# schematicEagle-CORRECTED.net
KiCad netlist of a schematic drawn in EAGLE
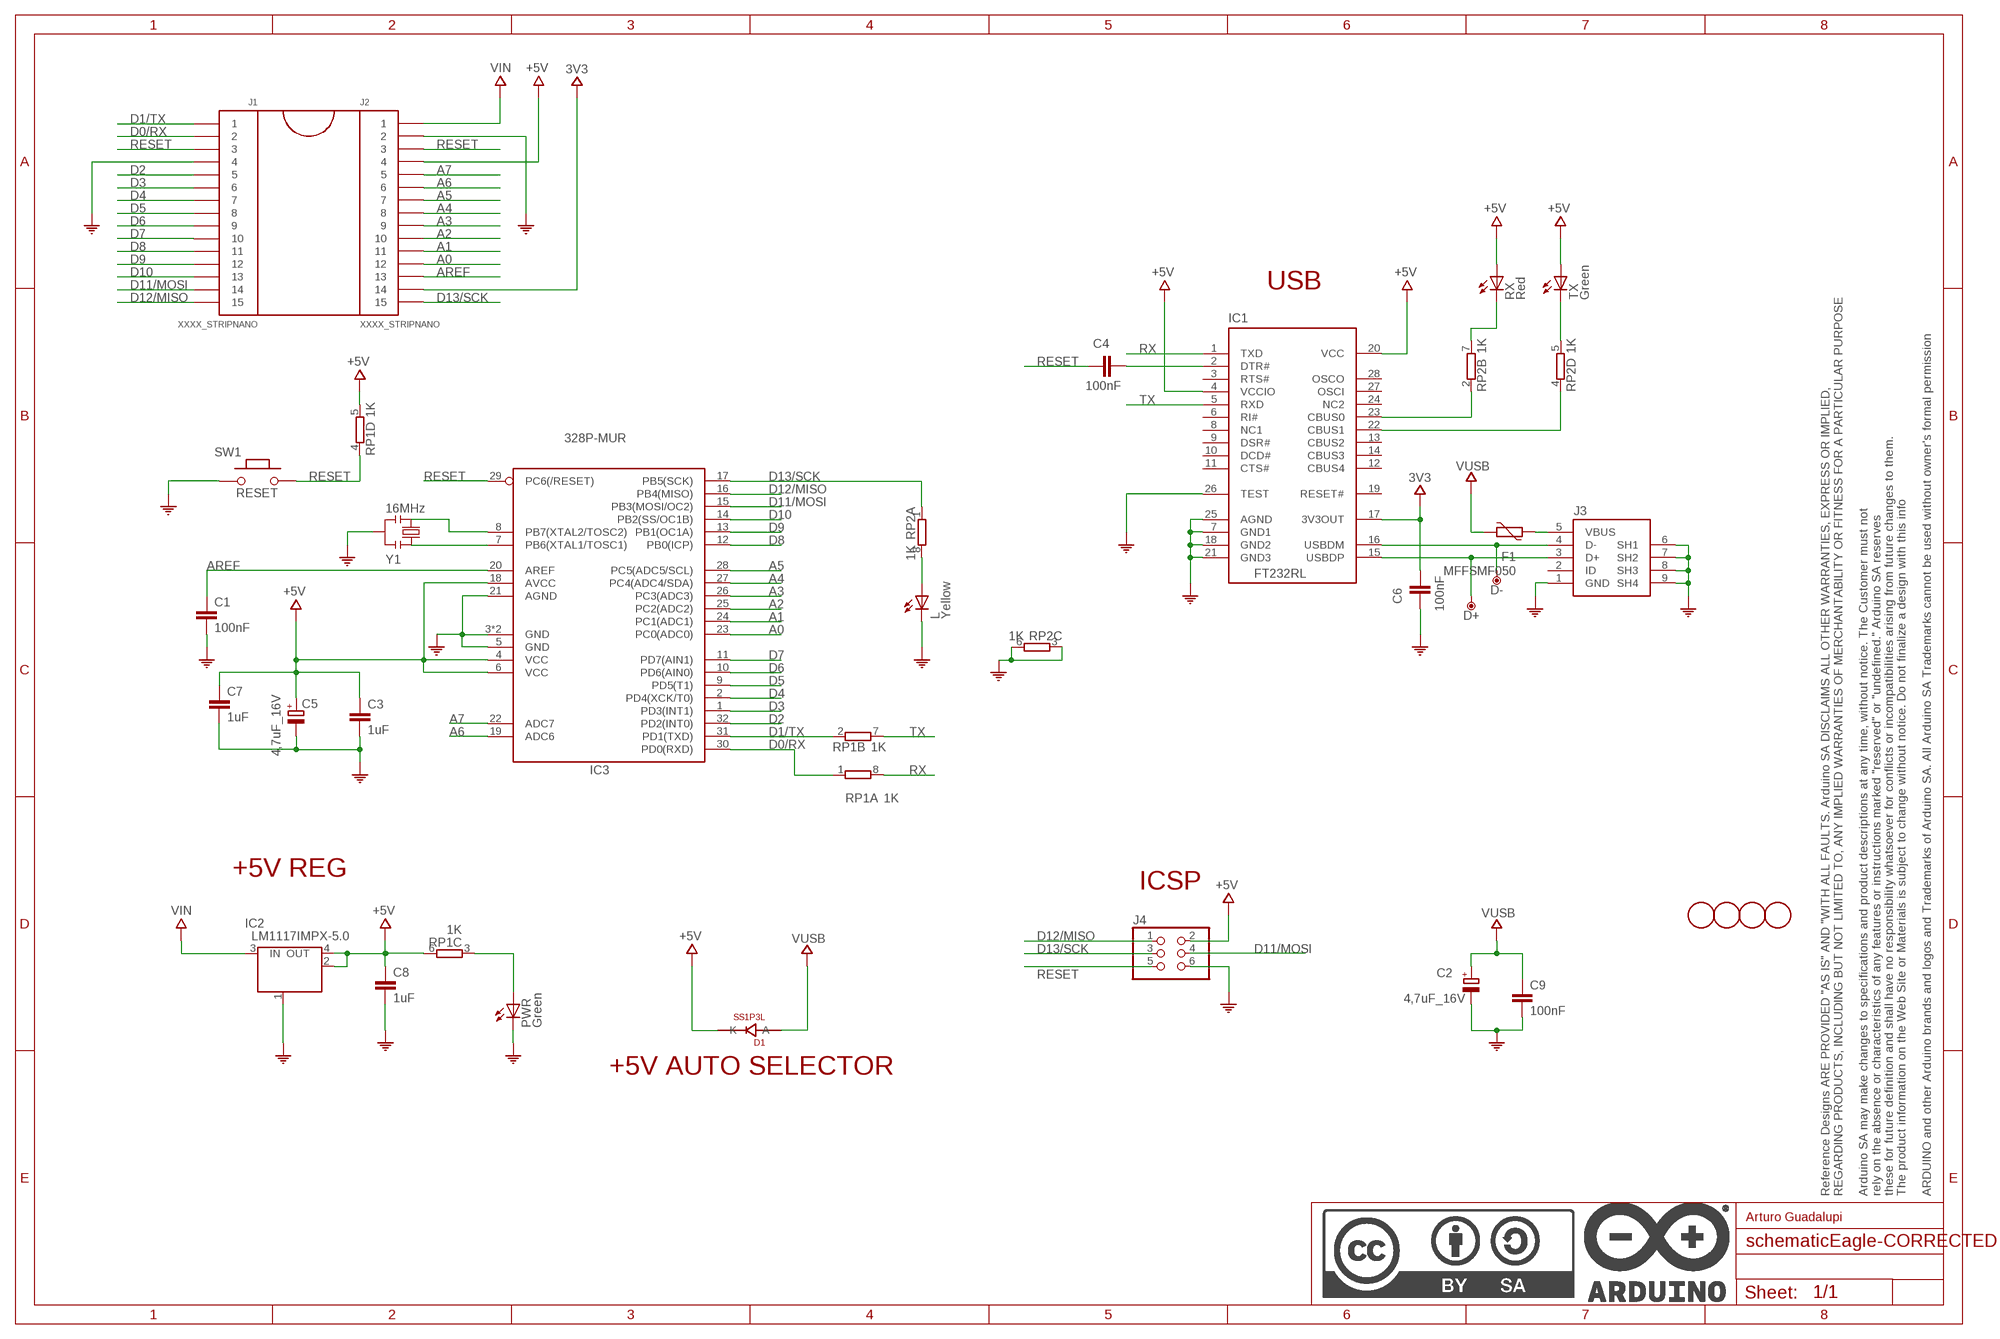
[diagram p0: schematic, sheet 1]

(export (version "E")
  (design (tool "Eeschema 10.0.6"))
  (components
    (comp (ref "C1")
      (value "100nF")
      (footprint "eagle-import:C0603-ROUND")
      (fields (field (name "PART_NUMBER") "cl10b104kbnc"))
      (libsource (lib "eagle-import") (part "0015_100NF_0603"))
    )
    (comp (ref "C2")
      (value "4,7uF_16V")
      (footprint "eagle-import:TAN-A")
      (fields (field (name "PART_NUMBER") "TAJA475MO16RNJ"))
      (libsource (lib "eagle-import") (part "0833_TAJA475MO16RNJ"))
    )
    (comp (ref "C3")
      (value "1uF")
      (footprint "eagle-import:C0603-ROUND")
      (fields (field (name "PART_NUMBER") "1uF_0603/GRM188R61E105KA12D"))
      (libsource (lib "eagle-import") (part "0006_1UF_0603/GRM188R61E105KA12D"))
    )
    (comp (ref "C4")
      (value "100nF")
      (footprint "eagle-import:C0603-ROUND")
      (fields (field (name "PART_NUMBER") "cl10b104kbnc"))
      (libsource (lib "eagle-import") (part "0015_100NF_0603"))
    )
    (comp (ref "C5")
      (value "4,7uF_16V")
      (footprint "eagle-import:TAN-A")
      (fields (field (name "PART_NUMBER") "TAJA475MO16RNJ"))
      (libsource (lib "eagle-import") (part "0833_TAJA475MO16RNJ"))
    )
    (comp (ref "C6")
      (value "100nF")
      (footprint "eagle-import:C0603-ROUND")
      (fields (field (name "PART_NUMBER") "cl10b104kbnc"))
      (libsource (lib "eagle-import") (part "0015_100NF_0603"))
    )
    (comp (ref "C7")
      (value "1uF")
      (footprint "eagle-import:C0603-ROUND")
      (fields (field (name "PART_NUMBER") "1uF_0603/GRM188R61E105KA12D"))
      (libsource (lib "eagle-import") (part "0006_1UF_0603/GRM188R61E105KA12D"))
    )
    (comp (ref "C8")
      (value "1uF")
      (footprint "eagle-import:C0603-ROUND")
      (fields (field (name "PART_NUMBER") "1uF_0603/GRM188R61E105KA12D"))
      (libsource (lib "eagle-import") (part "0006_1UF_0603/GRM188R61E105KA12D"))
    )
    (comp (ref "C9")
      (value "100nF")
      (footprint "eagle-import:C0603-ROUND")
      (fields (field (name "PART_NUMBER") "cl10b104kbnc"))
      (libsource (lib "eagle-import") (part "0015_100NF_0603"))
    )
    (comp (ref "D+")
      (value "DNP")
      (footprint "eagle-import:TP-1.00MM")
      (libsource (lib "eagle-import") (part "TPTP-1.00MM"))
    )
    (comp (ref "D-")
      (value "DNP")
      (footprint "eagle-import:TP-1.00MM")
      (libsource (lib "eagle-import") (part "TPTP-1.00MM"))
    )
    (comp (ref "D1")
      (value "SS1P3L")
      (footprint "eagle-import:DO220AAL")
      (fields (field (name "PART_NUMBER") "SS1P3L-M3/84A"))
      (libsource (lib "eagle-import") (part "0025_SS1P3L-M3/84A"))
    )
    (comp (ref "F1")
      (value "MFFSMF050")
      (footprint "eagle-import:0603-1608X90N")
      (fields (field (name "MANUFACTURER") "Bourns Inc "))
      (libsource (lib "eagle-import") (part "PTC"))
    )
    (comp (ref "FRAME1")
      (value "DNP")
      (footprint "eagle-import:FRAME")
      (libsource (lib "eagle-import") (part "A3-FRAME"))
    )
    (comp (ref "IC1")
      (value "FT232RL")
      (footprint "eagle-import:SSOP28")
      (libsource (lib "eagle-import") (part "0226_FT232RL"))
    )
    (comp (ref "IC2")
      (value "LM1117IMPX-5.0")
      (footprint "eagle-import:LINEAR_SOT223")
      (libsource (lib "eagle-import") (part "0022_LM1117IMPX-5.0"))
    )
    (comp (ref "IC3")
      (value "328P-MUR")
      (footprint "eagle-import:VQFN32")
      (fields (field (name "MANUFACTURER") "ATMEL"))
      (libsource (lib "eagle-import") (part "ATMEGA328P-32MUR"))
    )
    (comp (ref "J1")
      (value "XXXX_STRIPNANO")
      (footprint "eagle-import:HEAD15-NOSS")
      (libsource (lib "eagle-import") (part "XXXX_STRIPNANO"))
    )
    (comp (ref "J2")
      (value "XXXX_STRIPNANO")
      (footprint "eagle-import:HEAD15-NOSS")
      (libsource (lib "eagle-import") (part "XXXX_STRIPNANO"))
    )
    (comp (ref "J3")
      (value "0219_14850")
      (footprint "eagle-import:USB-MINI-B_2")
      (fields (field (name "PART_NUMBER") "14850"))
      (libsource (lib "eagle-import") (part "0219_14850"))
    )
    (comp (ref "J4")
      (value "0114_PH254-203DF118A00V")
      (footprint "eagle-import:2X03")
      (fields (field (name "PART_NUMBER") "PH254-203DF118A00V"))
      (libsource (lib "eagle-import") (part "0114_PH254-203DF118A00V"))
    )
    (comp (ref "L")
      (value "Yellow")
      (footprint "eagle-import:CHIPLED_0805")
      (fields (field (name "PART_NUMBER") "KPT-2012YC"))
      (libsource (lib "eagle-import") (part "0044_KPT-2012YC"))
    )
    (comp (ref "PWR")
      (value "Green")
      (footprint "eagle-import:CHIPLED_0805")
      (fields (field (name "PART_NUMBER") "KPT-2012SGC"))
      (libsource (lib "eagle-import") (part "0043_KPT-2012SGC"))
    )
    (comp (ref "RP1")
      (value "1K")
      (footprint "eagle-import:CAY16")
      (fields (field (name "PART_NUMBER") "064R_1K_/_CAY16-102J4LF"))
      (libsource (lib "eagle-import") (part "0005_064R_1K_/_CAY16-102J4LF"))
    )
    (comp (ref "RP2")
      (value "1K")
      (footprint "eagle-import:CAY16")
      (fields (field (name "PART_NUMBER") "064R_1K_/_CAY16-102J4LF"))
      (libsource (lib "eagle-import") (part "0005_064R_1K_/_CAY16-102J4LF"))
    )
    (comp (ref "RX")
      (value "Red")
      (footprint "eagle-import:CHIPLED_0805")
      (fields (field (name "PART_NUMBER") "KTP-2012SURCK"))
      (libsource (lib "eagle-import") (part "0181_KTP-2012SURCK"))
    )
    (comp (ref "SW1")
      (value "RESET")
      (footprint "eagle-import:SMD_157SW")
      (fields (field (name "PART_NUMBER") "IT-1185AP1C-160G-G_T&R"))
      (libsource (lib "eagle-import") (part "0173_IT-1185AP1C-160G-G_T&R"))
    )
    (comp (ref "TX")
      (value "Green")
      (footprint "eagle-import:CHIPLED_0805")
      (fields (field (name "PART_NUMBER") "KPT-2012SGC"))
      (libsource (lib "eagle-import") (part "0043_KPT-2012SGC"))
    )
    (comp (ref "U$4")
      (value "DNP")
      (footprint "eagle-import:FD-1-1.5")
      (libsource (lib "eagle-import") (part "FIDUCIAL-1.5MM"))
    )
    (comp (ref "U$5")
      (value "DNP")
      (footprint "eagle-import:FD-1-1.5")
      (libsource (lib "eagle-import") (part "FIDUCIAL-1.5MM"))
    )
    (comp (ref "U$53")
      (value "DNP")
      (footprint "eagle-import:FD-1-1.5")
      (libsource (lib "eagle-import") (part "FIDUCIAL-1.5MM"))
    )
    (comp (ref "U$54")
      (value "DNP")
      (footprint "eagle-import:FD-1-1.5")
      (libsource (lib "eagle-import") (part "FIDUCIAL-1.5MM"))
    )
    (comp (ref "Y1")
      (value "16MHz")
      (footprint "eagle-import:RESONATOR")
      (fields (field (name "PART_NUMBER") "CSTCE16M0V53-R0"))
      (libsource (lib "eagle-import") (part "0011_CSTCE16M0V53-R0"))
    )
  )
  (nets
    (net (code "1") (name "+5V") (class "Default")
      (node (ref "C3") (pin "1") (pinfunction "1_1") (pintype "passive"))
      (node (ref "C5") (pin "1") (pinfunction "+_1") (pintype "passive"))
      (node (ref "C7") (pin "1") (pinfunction "1_1") (pintype "passive"))
      (node (ref "C8") (pin "1") (pinfunction "1_1") (pintype "passive"))
      (node (ref "D1") (pin "P$1") (pinfunction "K_P$1") (pintype "bidirectional"))
      (node (ref "IC1") (pin "20") (pinfunction "VCC_20") (pintype "power_in"))
      (node (ref "IC1") (pin "4") (pinfunction "VCCIO_4") (pintype "power_in"))
      (node (ref "IC2") (pin "2") (pinfunction "OUT_2") (pintype "passive"))
      (node (ref "IC2") (pin "4") (pinfunction "OUT_4") (pintype "passive"))
      (node (ref "IC3") (pin "18") (pinfunction "AVCC_18") (pintype "bidirectional"))
      (node (ref "IC3") (pin "4") (pinfunction "VCC_4") (pintype "bidirectional"))
      (node (ref "IC3") (pin "6") (pinfunction "VCC_6") (pintype "bidirectional"))
      (node (ref "J2") (pin "4") (pinfunction "4_4") (pintype "passive"))
      (node (ref "J4") (pin "2") (pinfunction "2_2") (pintype "passive"))
      (node (ref "RP1") (pin "5") (pinfunction "2_5") (pintype "passive"))
      (node (ref "RP1") (pin "6") (pinfunction "2_6") (pintype "passive"))
      (node (ref "RX") (pin "A") (pinfunction "A_A") (pintype "passive"))
      (node (ref "TX") (pin "A") (pinfunction "A_A") (pintype "passive"))
    )
    (net (code "2") (name "/A0") (class "Default")
      (node (ref "IC3") (pin "23") (pinfunction "PC0(ADC0)_23") (pintype "bidirectional"))
      (node (ref "J2") (pin "12") (pinfunction "12_12") (pintype "passive"))
    )
    (net (code "3") (name "/A1") (class "Default")
      (node (ref "IC3") (pin "24") (pinfunction "PC1(ADC1)_24") (pintype "bidirectional"))
      (node (ref "J2") (pin "11") (pinfunction "11_11") (pintype "passive"))
    )
    (net (code "4") (name "/A2") (class "Default")
      (node (ref "IC3") (pin "25") (pinfunction "PC2(ADC2)_25") (pintype "bidirectional"))
      (node (ref "J2") (pin "10") (pinfunction "10_10") (pintype "passive"))
    )
    (net (code "5") (name "/A3") (class "Default")
      (node (ref "IC3") (pin "26") (pinfunction "PC3(ADC3)_26") (pintype "bidirectional"))
      (node (ref "J2") (pin "9") (pinfunction "9_9") (pintype "passive"))
    )
    (net (code "6") (name "/A4") (class "Default")
      (node (ref "IC3") (pin "27") (pinfunction "PC4(ADC4/SDA)_27") (pintype "bidirectional"))
      (node (ref "J2") (pin "8") (pinfunction "8_8") (pintype "passive"))
    )
    (net (code "7") (name "/A5") (class "Default")
      (node (ref "IC3") (pin "28") (pinfunction "PC5(ADC5/SCL)_28") (pintype "bidirectional"))
      (node (ref "J2") (pin "7") (pinfunction "7_7") (pintype "passive"))
    )
    (net (code "8") (name "/A6") (class "Default")
      (node (ref "IC3") (pin "19") (pinfunction "ADC6_19") (pintype "bidirectional"))
      (node (ref "J2") (pin "6") (pinfunction "6_6") (pintype "passive"))
    )
    (net (code "9") (name "/A7") (class "Default")
      (node (ref "IC3") (pin "22") (pinfunction "ADC7_22") (pintype "bidirectional"))
      (node (ref "J2") (pin "5") (pinfunction "5_5") (pintype "passive"))
    )
    (net (code "10") (name "/AREF") (class "Default")
      (node (ref "C1") (pin "1") (pinfunction "1_1") (pintype "passive"))
      (node (ref "IC3") (pin "20") (pinfunction "AREF_20") (pintype "bidirectional"))
      (node (ref "J2") (pin "13") (pinfunction "13_13") (pintype "passive"))
    )
    (net (code "11") (name "/D0{slash}RX") (class "Default")
      (node (ref "IC3") (pin "30") (pinfunction "PD0(RXD)_30") (pintype "bidirectional"))
      (node (ref "J1") (pin "2") (pinfunction "2_2") (pintype "passive"))
      (node (ref "RP1") (pin "1") (pinfunction "1_1") (pintype "passive"))
    )
    (net (code "12") (name "/D1{slash}TX") (class "Default")
      (node (ref "IC3") (pin "31") (pinfunction "PD1(TXD)_31") (pintype "bidirectional"))
      (node (ref "J1") (pin "1") (pinfunction "1_1") (pintype "passive"))
      (node (ref "RP1") (pin "2") (pinfunction "1_2") (pintype "passive"))
    )
    (net (code "13") (name "/D2") (class "Default")
      (node (ref "IC3") (pin "32") (pinfunction "PD2(INT0)_32") (pintype "bidirectional"))
      (node (ref "J1") (pin "5") (pinfunction "5_5") (pintype "passive"))
    )
    (net (code "14") (name "/D3") (class "Default")
      (node (ref "IC3") (pin "1") (pinfunction "PD3(INT1)_1") (pintype "bidirectional"))
      (node (ref "J1") (pin "6") (pinfunction "6_6") (pintype "passive"))
    )
    (net (code "15") (name "/D4") (class "Default")
      (node (ref "IC3") (pin "2") (pinfunction "PD4(XCK/T0)_2") (pintype "bidirectional"))
      (node (ref "J1") (pin "7") (pinfunction "7_7") (pintype "passive"))
    )
    (net (code "16") (name "/D5") (class "Default")
      (node (ref "IC3") (pin "9") (pinfunction "PD5(T1)_9") (pintype "bidirectional"))
      (node (ref "J1") (pin "8") (pinfunction "8_8") (pintype "passive"))
    )
    (net (code "17") (name "/D6") (class "Default")
      (node (ref "IC3") (pin "10") (pinfunction "PD6(AIN0)_10") (pintype "bidirectional"))
      (node (ref "J1") (pin "9") (pinfunction "9_9") (pintype "passive"))
    )
    (net (code "18") (name "/D7") (class "Default")
      (node (ref "IC3") (pin "11") (pinfunction "PD7(AIN1)_11") (pintype "bidirectional"))
      (node (ref "J1") (pin "10") (pinfunction "10_10") (pintype "passive"))
    )
    (net (code "19") (name "/D8") (class "Default")
      (node (ref "IC3") (pin "12") (pinfunction "PB0(ICP)_12") (pintype "bidirectional"))
      (node (ref "J1") (pin "11") (pinfunction "11_11") (pintype "passive"))
    )
    (net (code "20") (name "/D9") (class "Default")
      (node (ref "IC3") (pin "13") (pinfunction "PB1(OC1A)_13") (pintype "bidirectional"))
      (node (ref "J1") (pin "12") (pinfunction "12_12") (pintype "passive"))
    )
    (net (code "21") (name "/D10") (class "Default")
      (node (ref "IC3") (pin "14") (pinfunction "PB2(SS/OC1B)_14") (pintype "bidirectional"))
      (node (ref "J1") (pin "13") (pinfunction "13_13") (pintype "passive"))
    )
    (net (code "22") (name "/D11{slash}MOSI") (class "Default")
      (node (ref "IC3") (pin "15") (pinfunction "PB3(MOSI/OC2)_15") (pintype "bidirectional"))
      (node (ref "J1") (pin "14") (pinfunction "14_14") (pintype "passive"))
      (node (ref "J4") (pin "4") (pinfunction "4_4") (pintype "passive"))
    )
    (net (code "23") (name "/D12{slash}MISO") (class "Default")
      (node (ref "IC3") (pin "16") (pinfunction "PB4(MISO)_16") (pintype "bidirectional"))
      (node (ref "J1") (pin "15") (pinfunction "15_15") (pintype "passive"))
      (node (ref "J4") (pin "1") (pinfunction "1_1") (pintype "passive"))
    )
    (net (code "24") (name "/D13{slash}SCK") (class "Default")
      (node (ref "IC3") (pin "17") (pinfunction "PB5(SCK)_17") (pintype "bidirectional"))
      (node (ref "J2") (pin "15") (pinfunction "15_15") (pintype "passive"))
      (node (ref "J4") (pin "3") (pinfunction "3_3") (pintype "passive"))
      (node (ref "RP2") (pin "1") (pinfunction "1_1") (pintype "passive"))
    )
    (net (code "25") (name "/RESET") (class "Default")
      (node (ref "C4") (pin "1") (pinfunction "1_1") (pintype "passive"))
      (node (ref "IC3") (pin "29") (pinfunction "PC6(/RESET)_29") (pintype "bidirectional"))
      (node (ref "J1") (pin "3") (pinfunction "3_3") (pintype "passive"))
      (node (ref "J2") (pin "3") (pinfunction "3_3") (pintype "passive"))
      (node (ref "J4") (pin "5") (pinfunction "5_5") (pintype "passive"))
      (node (ref "RP1") (pin "4") (pinfunction "1_4") (pintype "passive"))
      (node (ref "SW1") (pin "2") (pinfunction "2_2") (pintype "passive"))
    )
    (net (code "26") (name "/RX") (class "Default")
      (node (ref "IC1") (pin "1") (pinfunction "TXD_1") (pintype "output"))
      (node (ref "RP1") (pin "8") (pinfunction "2_8") (pintype "passive"))
    )
    (net (code "27") (name "/TX") (class "Default")
      (node (ref "IC1") (pin "5") (pinfunction "RXD_5") (pintype "input"))
      (node (ref "RP1") (pin "7") (pinfunction "2_7") (pintype "passive"))
    )
    (net (code "28") (name "3V3") (class "Default")
      (node (ref "C6") (pin "2") (pinfunction "2_2") (pintype "passive"))
      (node (ref "IC1") (pin "17") (pinfunction "3V3OUT_17") (pintype "power_in"))
      (node (ref "J2") (pin "14") (pinfunction "14_14") (pintype "passive"))
    )
    (net (code "29") (name "COM") (class "Default")
      (node (ref "C1") (pin "2") (pinfunction "2_2") (pintype "passive"))
      (node (ref "C2") (pin "2") (pinfunction "-_2") (pintype "passive"))
      (node (ref "C3") (pin "2") (pinfunction "2_2") (pintype "passive"))
      (node (ref "C5") (pin "2") (pinfunction "-_2") (pintype "passive"))
      (node (ref "C6") (pin "1") (pinfunction "1_1") (pintype "passive"))
      (node (ref "C7") (pin "2") (pinfunction "2_2") (pintype "passive"))
      (node (ref "C8") (pin "2") (pinfunction "2_2") (pintype "passive"))
      (node (ref "C9") (pin "2") (pinfunction "2_2") (pintype "passive"))
      (node (ref "IC1") (pin "18") (pinfunction "GND2_18") (pintype "power_in"))
      (node (ref "IC1") (pin "21") (pinfunction "GND3_21") (pintype "power_in"))
      (node (ref "IC1") (pin "25") (pinfunction "AGND_25") (pintype "power_in"))
      (node (ref "IC1") (pin "26") (pinfunction "TEST_26") (pintype "bidirectional"))
      (node (ref "IC1") (pin "7") (pinfunction "GND1_7") (pintype "power_in"))
      (node (ref "IC2") (pin "1") (pinfunction "GND/ADJ_1") (pintype "input"))
      (node (ref "IC3") (pin "21") (pinfunction "AGND_21") (pintype "bidirectional"))
      (node (ref "IC3") (pin "3") (pinfunction "GND_3") (pintype "bidirectional"))
      (node (ref "IC3") (pin "33") (pinfunction "GND_33") (pintype "bidirectional"))
      (node (ref "IC3") (pin "5") (pinfunction "GND_5") (pintype "bidirectional"))
      (node (ref "J1") (pin "4") (pinfunction "4_4") (pintype "passive"))
      (node (ref "J2") (pin "2") (pinfunction "2_2") (pintype "passive"))
      (node (ref "J3") (pin "1") (pinfunction "GND_1") (pintype "passive"))
      (node (ref "J3") (pin "6") (pinfunction "SH1_6") (pintype "passive"))
      (node (ref "J3") (pin "7") (pinfunction "SH2_7") (pintype "passive"))
      (node (ref "J3") (pin "8") (pinfunction "SH3_8") (pintype "passive"))
      (node (ref "J3") (pin "9") (pinfunction "SH4_9") (pintype "passive"))
      (node (ref "J4") (pin "6") (pinfunction "6_6") (pintype "passive"))
      (node (ref "L") (pin "C") (pinfunction "C_C") (pintype "passive"))
      (node (ref "PWR") (pin "C") (pinfunction "C_C") (pintype "passive"))
      (node (ref "RP2") (pin "3") (pinfunction "1_3") (pintype "passive"))
      (node (ref "RP2") (pin "6") (pinfunction "2_6") (pintype "passive"))
      (node (ref "SW1") (pin "1") (pinfunction "1_1") (pintype "passive"))
      (node (ref "Y1") (pin "2") (pinfunction "2_2") (pintype "passive"))
    )
    (net (code "30") (name "Net-(D+-P$1)") (class "Default")
      (node (ref "D+") (pin "X") (pinfunction "P$1_X") (pintype "passive"))
      (node (ref "IC1") (pin "15") (pinfunction "USBDP_15") (pintype "bidirectional"))
      (node (ref "J3") (pin "3") (pinfunction "D+_3") (pintype "bidirectional"))
    )
    (net (code "31") (name "Net-(D--P$1)") (class "Default")
      (node (ref "D-") (pin "X") (pinfunction "P$1_X") (pintype "passive"))
      (node (ref "IC1") (pin "16") (pinfunction "USBDM_16") (pintype "bidirectional"))
      (node (ref "J3") (pin "4") (pinfunction "D-_4") (pintype "bidirectional"))
    )
    (net (code "32") (name "Net-(IC1-CBUS0)") (class "Default")
      (node (ref "IC1") (pin "23") (pinfunction "CBUS0_23") (pintype "bidirectional"))
      (node (ref "RP2") (pin "2") (pinfunction "1_2") (pintype "passive"))
    )
    (net (code "33") (name "Net-(IC1-CBUS1)") (class "Default")
      (node (ref "IC1") (pin "22") (pinfunction "CBUS1_22") (pintype "bidirectional"))
      (node (ref "RP2") (pin "4") (pinfunction "1_4") (pintype "passive"))
    )
    (net (code "34") (name "Net-(IC1-DTR#)") (class "Default")
      (node (ref "C4") (pin "2") (pinfunction "2_2") (pintype "passive"))
      (node (ref "IC1") (pin "2") (pinfunction "DTR#_2") (pintype "output"))
    )
    (net (code "35") (name "Net-(IC3-PB6(XTAL1{slash}TOSC1))") (class "Default")
      (node (ref "IC3") (pin "7") (pinfunction "PB6(XTAL1/TOSC1)_7") (pintype "bidirectional"))
      (node (ref "Y1") (pin "1") (pinfunction "1_1") (pintype "passive"))
    )
    (net (code "36") (name "Net-(IC3-PB7(XTAL2{slash}TOSC2))") (class "Default")
      (node (ref "IC3") (pin "8") (pinfunction "PB7(XTAL2/TOSC2)_8") (pintype "bidirectional"))
      (node (ref "Y1") (pin "3") (pinfunction "3_3") (pintype "passive"))
    )
    (net (code "37") (name "Net-(J3-VBUS)") (class "Default")
      (node (ref "F1") (pin "2") (pinfunction "2_2") (pintype "passive"))
      (node (ref "J3") (pin "5") (pinfunction "VBUS_5") (pintype "power_in"))
    )
    (net (code "38") (name "Net-(RP1C-1)") (class "Default")
      (node (ref "PWR") (pin "A") (pinfunction "A_A") (pintype "passive"))
      (node (ref "RP1") (pin "3") (pinfunction "1_3") (pintype "passive"))
    )
    (net (code "39") (name "Net-(RP2A-2)") (class "Default")
      (node (ref "L") (pin "A") (pinfunction "A_A") (pintype "passive"))
      (node (ref "RP2") (pin "8") (pinfunction "2_8") (pintype "passive"))
    )
    (net (code "40") (name "Net-(RP2B-2)") (class "Default")
      (node (ref "RP2") (pin "7") (pinfunction "2_7") (pintype "passive"))
      (node (ref "RX") (pin "C") (pinfunction "C_C") (pintype "passive"))
    )
    (net (code "41") (name "Net-(RP2D-2)") (class "Default")
      (node (ref "RP2") (pin "5") (pinfunction "2_5") (pintype "passive"))
      (node (ref "TX") (pin "C") (pinfunction "C_C") (pintype "passive"))
    )
    (net (code "42") (name "VIN") (class "Default")
      (node (ref "IC2") (pin "3") (pinfunction "IN_3") (pintype "input"))
      (node (ref "J2") (pin "1") (pinfunction "1_1") (pintype "passive"))
    )
    (net (code "43") (name "VUSB") (class "Default")
      (node (ref "C2") (pin "1") (pinfunction "+_1") (pintype "passive"))
      (node (ref "C9") (pin "1") (pinfunction "1_1") (pintype "passive"))
      (node (ref "D1") (pin "P$2") (pinfunction "A_P$2") (pintype "bidirectional"))
      (node (ref "F1") (pin "1") (pinfunction "1_1") (pintype "passive"))
    )
    (net (code "44") (name "unconnected-(IC1-CBUS2-Pad13)") (class "Default")
      (node (ref "IC1") (pin "13") (pinfunction "CBUS2_13") (pintype "bidirectional"))
    )
    (net (code "45") (name "unconnected-(IC1-CBUS3-Pad14)") (class "Default")
      (node (ref "IC1") (pin "14") (pinfunction "CBUS3_14") (pintype "bidirectional"))
    )
    (net (code "46") (name "unconnected-(IC1-CBUS4-Pad12)") (class "Default")
      (node (ref "IC1") (pin "12") (pinfunction "CBUS4_12") (pintype "bidirectional"))
    )
    (net (code "47") (name "unconnected-(IC1-CTS#-Pad11)") (class "Default")
      (node (ref "IC1") (pin "11") (pinfunction "CTS#_11") (pintype "bidirectional"))
    )
    (net (code "48") (name "unconnected-(IC1-DCD#-Pad10)") (class "Default")
      (node (ref "IC1") (pin "10") (pinfunction "DCD#_10") (pintype "bidirectional"))
    )
    (net (code "49") (name "unconnected-(IC1-DSR#-Pad9)") (class "Default")
      (node (ref "IC1") (pin "9") (pinfunction "DSR#_9") (pintype "bidirectional"))
    )
    (net (code "50") (name "unconnected-(IC1-NC1-Pad8)") (class "Default")
      (node (ref "IC1") (pin "8") (pinfunction "NC1_8") (pintype "bidirectional"))
    )
    (net (code "51") (name "unconnected-(IC1-NC2-Pad24)") (class "Default")
      (node (ref "IC1") (pin "24") (pinfunction "NC2_24") (pintype "no_connect"))
    )
    (net (code "52") (name "unconnected-(IC1-OSCI-Pad27)") (class "Default")
      (node (ref "IC1") (pin "27") (pinfunction "OSCI_27") (pintype "bidirectional"))
    )
    (net (code "53") (name "unconnected-(IC1-OSCO-Pad28)") (class "Default")
      (node (ref "IC1") (pin "28") (pinfunction "OSCO_28") (pintype "output"))
    )
    (net (code "54") (name "unconnected-(IC1-RESET#-Pad19)") (class "Default")
      (node (ref "IC1") (pin "19") (pinfunction "RESET#_19") (pintype "bidirectional"))
    )
    (net (code "55") (name "unconnected-(IC1-RI#-Pad6)") (class "Default")
      (node (ref "IC1") (pin "6") (pinfunction "RI#_6") (pintype "bidirectional"))
    )
    (net (code "56") (name "unconnected-(IC1-RTS#-Pad3)") (class "Default")
      (node (ref "IC1") (pin "3") (pinfunction "RTS#_3") (pintype "output"))
    )
    (net (code "57") (name "unconnected-(J3-ID-Pad2)") (class "Default")
      (node (ref "J3") (pin "2") (pinfunction "ID_2") (pintype "bidirectional"))
    )
  )
)
